# number_1.net
KiCad netlist of a schematic drawn in EAGLE
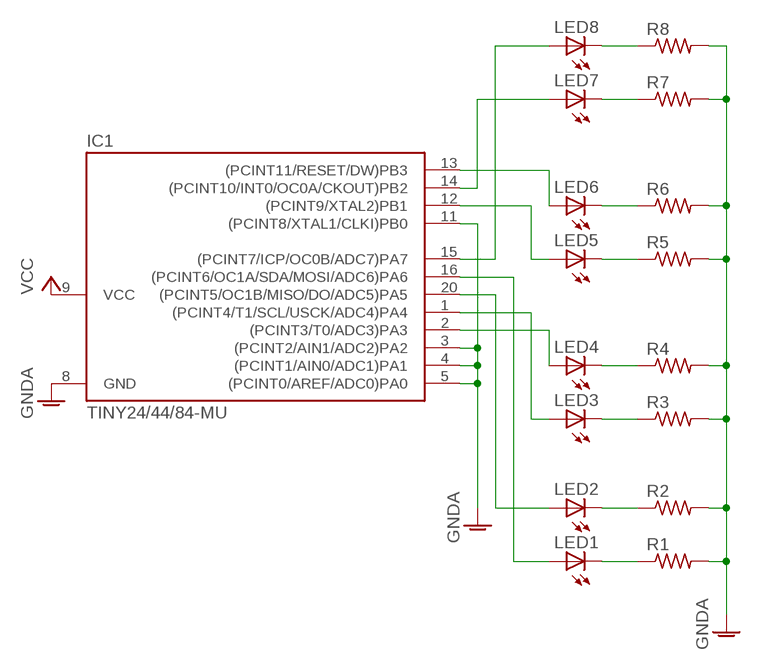
[diagram p0: schematic, sheet 1]

(export (version "E")
  (design (tool "Eeschema 10.0.6"))
  (components
    (comp (ref "IC1")
      (value "TINY24/44/84-MU")
      (footprint "eagle-import:QFN_MLF20")
      (libsource (lib "eagle-import") (part "TINY24/44/84-MU"))
    )
    (comp (ref "LED1")
      (value "LEDCHIP-LED0603")
      (footprint "eagle-import:CHIP-LED0603")
      (libsource (lib "eagle-import") (part "LEDCHIP-LED0603"))
    )
    (comp (ref "LED2")
      (value "LEDCHIP-LED0603")
      (footprint "eagle-import:CHIP-LED0603")
      (libsource (lib "eagle-import") (part "LEDCHIP-LED0603"))
    )
    (comp (ref "LED3")
      (value "LEDCHIP-LED0603")
      (footprint "eagle-import:CHIP-LED0603")
      (libsource (lib "eagle-import") (part "LEDCHIP-LED0603"))
    )
    (comp (ref "LED4")
      (value "LEDCHIP-LED0603")
      (footprint "eagle-import:CHIP-LED0603")
      (libsource (lib "eagle-import") (part "LEDCHIP-LED0603"))
    )
    (comp (ref "LED5")
      (value "LEDCHIP-LED0603")
      (footprint "eagle-import:CHIP-LED0603")
      (libsource (lib "eagle-import") (part "LEDCHIP-LED0603"))
    )
    (comp (ref "LED6")
      (value "LEDCHIP-LED0603")
      (footprint "eagle-import:CHIP-LED0603")
      (libsource (lib "eagle-import") (part "LEDCHIP-LED0603"))
    )
    (comp (ref "LED7")
      (value "LEDCHIP-LED0603")
      (footprint "eagle-import:CHIP-LED0603")
      (libsource (lib "eagle-import") (part "LEDCHIP-LED0603"))
    )
    (comp (ref "LED8")
      (value "LEDCHIP-LED0603")
      (footprint "eagle-import:CHIP-LED0603")
      (libsource (lib "eagle-import") (part "LEDCHIP-LED0603"))
    )
    (comp (ref "R1")
      (value "R-US_R0603")
      (footprint "eagle-import:R0603")
      (libsource (lib "eagle-import") (part "R-US_R0603"))
    )
    (comp (ref "R2")
      (value "R-US_R0603")
      (footprint "eagle-import:R0603")
      (libsource (lib "eagle-import") (part "R-US_R0603"))
    )
    (comp (ref "R3")
      (value "R-US_R0603")
      (footprint "eagle-import:R0603")
      (libsource (lib "eagle-import") (part "R-US_R0603"))
    )
    (comp (ref "R4")
      (value "R-US_R0603")
      (footprint "eagle-import:R0603")
      (libsource (lib "eagle-import") (part "R-US_R0603"))
    )
    (comp (ref "R5")
      (value "R-US_R0603")
      (footprint "eagle-import:R0603")
      (libsource (lib "eagle-import") (part "R-US_R0603"))
    )
    (comp (ref "R6")
      (value "R-US_R0603")
      (footprint "eagle-import:R0603")
      (libsource (lib "eagle-import") (part "R-US_R0603"))
    )
    (comp (ref "R7")
      (value "R-US_R0603")
      (footprint "eagle-import:R0603")
      (libsource (lib "eagle-import") (part "R-US_R0603"))
    )
    (comp (ref "R8")
      (value "R-US_R0603")
      (footprint "eagle-import:R0603")
      (libsource (lib "eagle-import") (part "R-US_R0603"))
    )
  )
  (nets
    (net (code "1") (name "GNDA") (class "Default")
      (node (ref "IC1") (pin "11") (pinfunction "(PCINT8/XTAL1/CLKI)PB0_11") (pintype "bidirectional"))
      (node (ref "IC1") (pin "3") (pinfunction "(PCINT2/AIN1/ADC2)PA2_3") (pintype "bidirectional"))
      (node (ref "IC1") (pin "4") (pinfunction "(PCINT1/AIN0/ADC1)PA1_4") (pintype "bidirectional"))
      (node (ref "IC1") (pin "5") (pinfunction "(PCINT0/AREF/ADC0)PA0_5") (pintype "bidirectional"))
      (node (ref "IC1") (pin "8") (pinfunction "GND_8") (pintype "power_in"))
      (node (ref "R1") (pin "2") (pinfunction "2_2") (pintype "passive"))
      (node (ref "R2") (pin "2") (pinfunction "2_2") (pintype "passive"))
      (node (ref "R3") (pin "2") (pinfunction "2_2") (pintype "passive"))
      (node (ref "R4") (pin "2") (pinfunction "2_2") (pintype "passive"))
      (node (ref "R5") (pin "2") (pinfunction "2_2") (pintype "passive"))
      (node (ref "R6") (pin "2") (pinfunction "2_2") (pintype "passive"))
      (node (ref "R7") (pin "2") (pinfunction "2_2") (pintype "passive"))
      (node (ref "R8") (pin "2") (pinfunction "2_2") (pintype "passive"))
    )
    (net (code "2") (name "Net-(IC1-(PCINT3{slash}T0{slash}ADC3)PA3)") (class "Default")
      (node (ref "IC1") (pin "2") (pinfunction "(PCINT3/T0/ADC3)PA3_2") (pintype "bidirectional"))
      (node (ref "LED4") (pin "A") (pinfunction "A_A") (pintype "passive"))
    )
    (net (code "3") (name "Net-(IC1-(PCINT4{slash}T1{slash}SCL{slash}USCK{slash}ADC4)PA4)") (class "Default")
      (node (ref "IC1") (pin "1") (pinfunction "(PCINT4/T1/SCL/USCK/ADC4)PA4_1") (pintype "bidirectional"))
      (node (ref "LED3") (pin "A") (pinfunction "A_A") (pintype "passive"))
    )
    (net (code "4") (name "Net-(IC1-(PCINT5{slash}OC1B{slash}MISO{slash}DO{slash}ADC5)PA5)") (class "Default")
      (node (ref "IC1") (pin "20") (pinfunction "(PCINT5/OC1B/MISO/DO/ADC5)PA5_20") (pintype "bidirectional"))
      (node (ref "LED2") (pin "A") (pinfunction "A_A") (pintype "passive"))
    )
    (net (code "5") (name "Net-(IC1-(PCINT6{slash}OC1A{slash}SDA{slash}MOSI{slash}ADC6)PA6)") (class "Default")
      (node (ref "IC1") (pin "16") (pinfunction "(PCINT6/OC1A/SDA/MOSI/ADC6)PA6_16") (pintype "bidirectional"))
      (node (ref "LED1") (pin "A") (pinfunction "A_A") (pintype "passive"))
    )
    (net (code "6") (name "Net-(IC1-(PCINT7{slash}ICP{slash}OC0B{slash}ADC7)PA7)") (class "Default")
      (node (ref "IC1") (pin "15") (pinfunction "(PCINT7/ICP/OC0B/ADC7)PA7_15") (pintype "bidirectional"))
      (node (ref "LED8") (pin "A") (pinfunction "A_A") (pintype "passive"))
    )
    (net (code "7") (name "Net-(IC1-(PCINT9{slash}XTAL2)PB1)") (class "Default")
      (node (ref "IC1") (pin "12") (pinfunction "(PCINT9/XTAL2)PB1_12") (pintype "bidirectional"))
      (node (ref "LED5") (pin "A") (pinfunction "A_A") (pintype "passive"))
    )
    (net (code "8") (name "Net-(IC1-(PCINT10{slash}INT0{slash}OC0A{slash}CKOUT)PB2)") (class "Default")
      (node (ref "IC1") (pin "14") (pinfunction "(PCINT10/INT0/OC0A/CKOUT)PB2_14") (pintype "bidirectional"))
      (node (ref "LED7") (pin "A") (pinfunction "A_A") (pintype "passive"))
    )
    (net (code "9") (name "Net-(IC1-(PCINT11{slash}RESET{slash}DW)PB3)") (class "Default")
      (node (ref "IC1") (pin "13") (pinfunction "(PCINT11/RESET/DW)PB3_13") (pintype "bidirectional"))
      (node (ref "LED6") (pin "A") (pinfunction "A_A") (pintype "passive"))
    )
    (net (code "10") (name "Net-(LED1-PadC)") (class "Default")
      (node (ref "LED1") (pin "C") (pinfunction "C_C") (pintype "passive"))
      (node (ref "R1") (pin "1") (pinfunction "1_1") (pintype "passive"))
    )
    (net (code "11") (name "Net-(LED2-PadC)") (class "Default")
      (node (ref "LED2") (pin "C") (pinfunction "C_C") (pintype "passive"))
      (node (ref "R2") (pin "1") (pinfunction "1_1") (pintype "passive"))
    )
    (net (code "12") (name "Net-(LED3-PadC)") (class "Default")
      (node (ref "LED3") (pin "C") (pinfunction "C_C") (pintype "passive"))
      (node (ref "R3") (pin "1") (pinfunction "1_1") (pintype "passive"))
    )
    (net (code "13") (name "Net-(LED4-PadC)") (class "Default")
      (node (ref "LED4") (pin "C") (pinfunction "C_C") (pintype "passive"))
      (node (ref "R4") (pin "1") (pinfunction "1_1") (pintype "passive"))
    )
    (net (code "14") (name "Net-(LED5-PadC)") (class "Default")
      (node (ref "LED5") (pin "C") (pinfunction "C_C") (pintype "passive"))
      (node (ref "R5") (pin "1") (pinfunction "1_1") (pintype "passive"))
    )
    (net (code "15") (name "Net-(LED6-PadC)") (class "Default")
      (node (ref "LED6") (pin "C") (pinfunction "C_C") (pintype "passive"))
      (node (ref "R6") (pin "1") (pinfunction "1_1") (pintype "passive"))
    )
    (net (code "16") (name "Net-(LED7-PadC)") (class "Default")
      (node (ref "LED7") (pin "C") (pinfunction "C_C") (pintype "passive"))
      (node (ref "R7") (pin "1") (pinfunction "1_1") (pintype "passive"))
    )
    (net (code "17") (name "Net-(LED8-PadC)") (class "Default")
      (node (ref "LED8") (pin "C") (pinfunction "C_C") (pintype "passive"))
      (node (ref "R8") (pin "1") (pinfunction "1_1") (pintype "passive"))
    )
    (net (code "18") (name "VCC") (class "Default")
      (node (ref "IC1") (pin "9") (pinfunction "VCC_9") (pintype "power_in"))
    )
  )
)
